# RS323_DB9.net
KiCad netlist of a schematic drawn in EAGLE
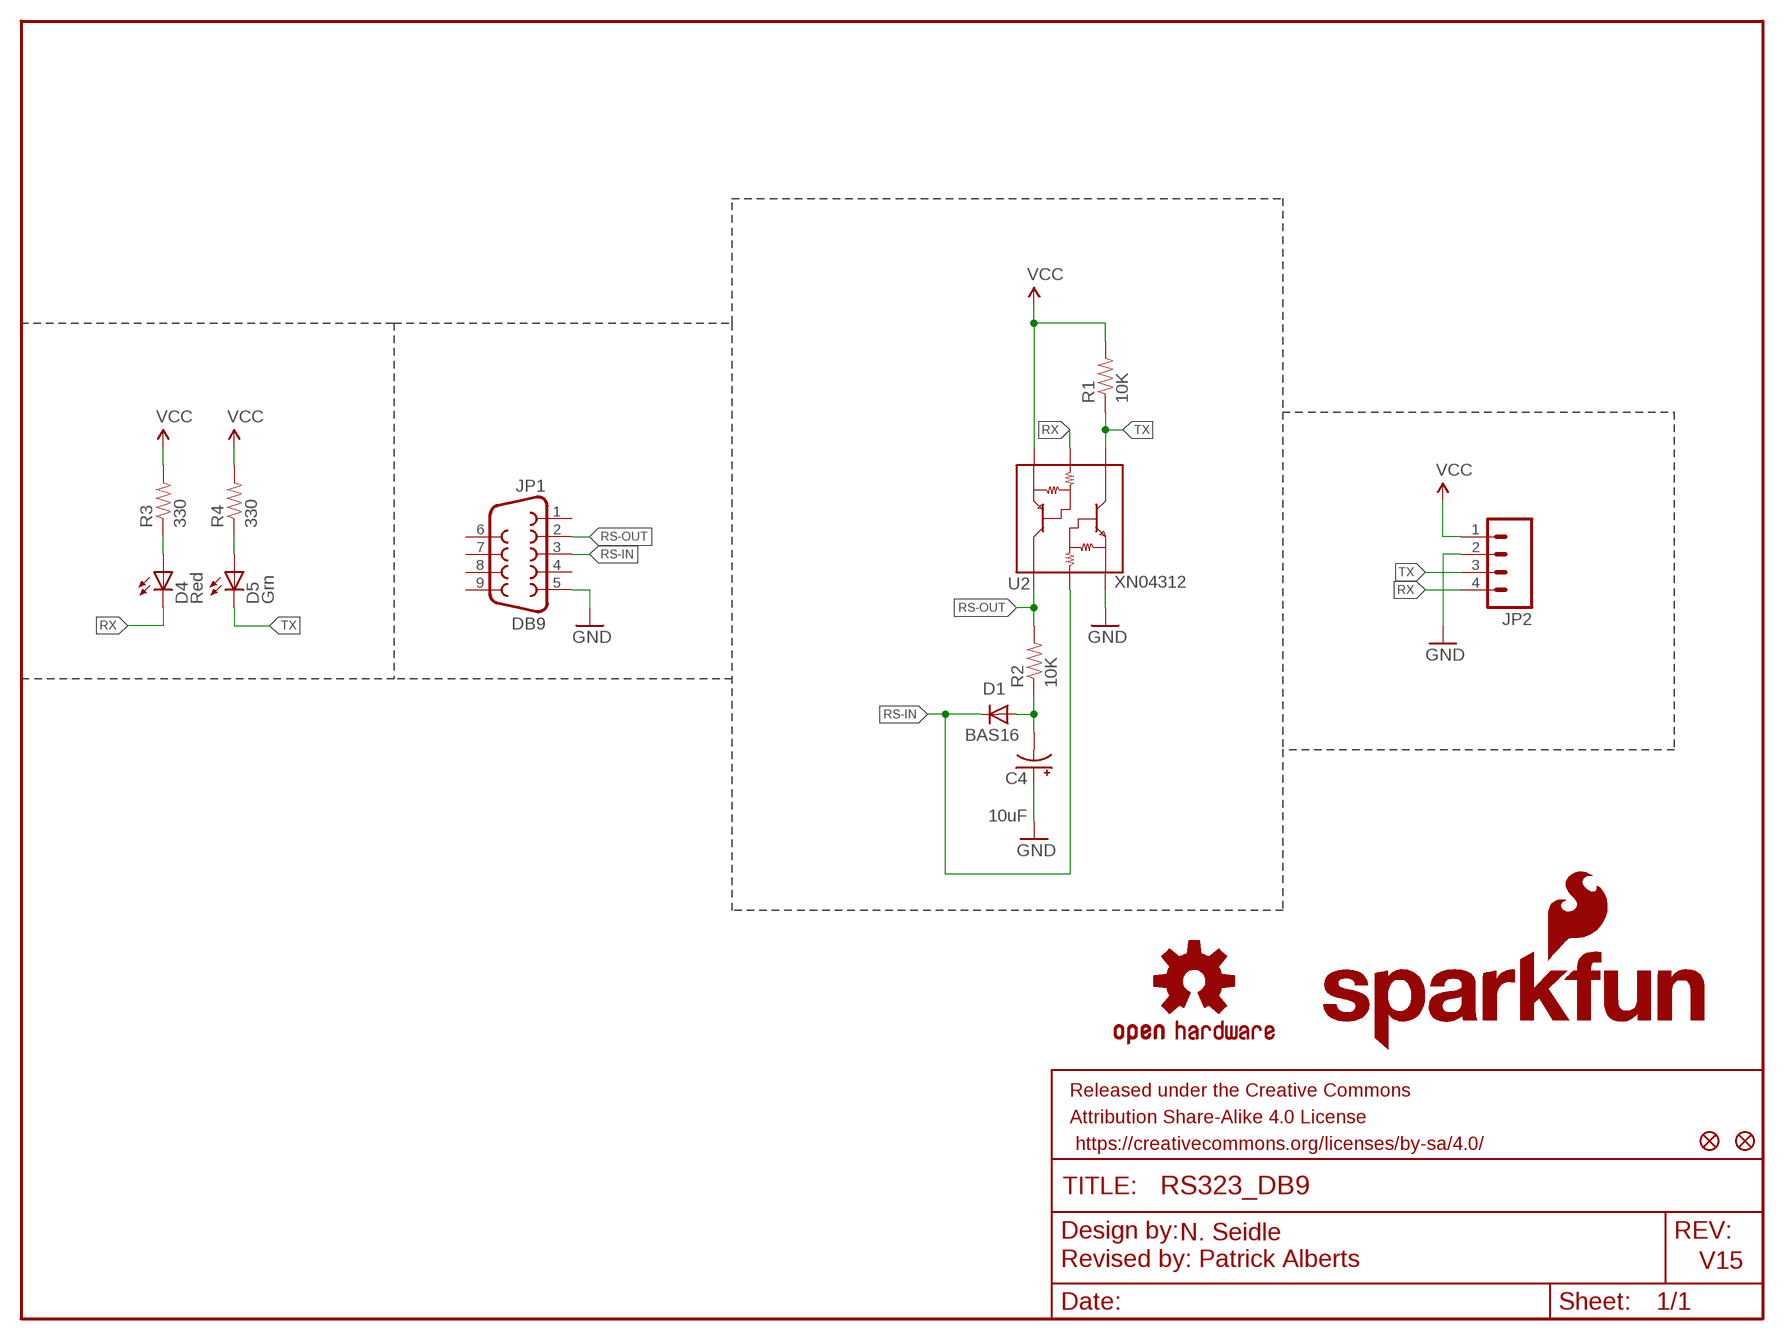
[diagram p0: schematic, sheet 1]

(export (version "E")
  (design (tool "Eeschema 10.0.6"))
  (components
    (comp (ref "C4")
      (value "10uF")
      (footprint "eagle-import:EIA3216")
      (libsource (lib "eagle-import") (part "CAP_POL1206"))
    )
    (comp (ref "D1")
      (value "BAS16")
      (footprint "eagle-import:SOD-323")
      (libsource (lib "eagle-import") (part "DIODESOD"))
    )
    (comp (ref "D4")
      (value "Red")
      (footprint "eagle-import:LED-1206")
      (libsource (lib "eagle-import") (part "LED1206"))
    )
    (comp (ref "D5")
      (value "Grn")
      (footprint "eagle-import:LED-1206")
      (libsource (lib "eagle-import") (part "LED1206"))
    )
    (comp (ref "E$1")
      (value "FIDUCIAL1X2")
      (footprint "eagle-import:FIDUCIAL-1X2")
      (libsource (lib "eagle-import") (part "FIDUCIAL1X2"))
    )
    (comp (ref "E$2")
      (value "FIDUCIAL1X2")
      (footprint "eagle-import:FIDUCIAL-1X2")
      (libsource (lib "eagle-import") (part "FIDUCIAL1X2"))
    )
    (comp (ref "FRAME1")
      (value "FRAME-LETTER")
      (footprint "eagle-import:CREATIVE_COMMONS")
      (fields (field (name "DESIGNER") "NAME"))
      (libsource (lib "eagle-import") (part "FRAME-LETTER"))
    )
    (comp (ref "JP1")
      (value "DB9")
      (footprint "eagle-import:DB9")
      (libsource (lib "eagle-import") (part "DB9FEMALE"))
    )
    (comp (ref "JP2")
      (value "M04PTH")
      (footprint "eagle-import:1X04")
      (libsource (lib "eagle-import") (part "M04PTH"))
    )
    (comp (ref "LOGO1")
      (value "SFE_LOGO_NAME_FLAME.1_INCH")
      (footprint "eagle-import:SFE_LOGO_NAME_FLAME_.1")
      (libsource (lib "eagle-import") (part "SFE_LOGO_NAME_FLAME.1_INCH"))
    )
    (comp (ref "LOGO2")
      (value "OSHW-LOGOM")
      (footprint "eagle-import:OSHW-LOGO-M")
      (libsource (lib "eagle-import") (part "OSHW-LOGOM"))
    )
    (comp (ref "R1")
      (value "10K")
      (footprint "eagle-import:0603-RES")
      (libsource (lib "eagle-import") (part "10KOHM1/10W1%(0603)0603"))
    )
    (comp (ref "R2")
      (value "10K")
      (footprint "eagle-import:0603-RES")
      (libsource (lib "eagle-import") (part "10KOHM1/10W1%(0603)0603"))
    )
    (comp (ref "R3")
      (value "330")
      (footprint "eagle-import:0603-RES")
      (libsource (lib "eagle-import") (part "330OHM1/10W1%(0603)"))
    )
    (comp (ref "R4")
      (value "330")
      (footprint "eagle-import:0603-RES")
      (libsource (lib "eagle-import") (part "330OHM1/10W1%(0603)"))
    )
    (comp (ref "U2")
      (value "XN04312")
      (footprint "eagle-import:SOT23-6")
      (libsource (lib "eagle-import") (part "XN04312SOT"))
    )
  )
  (nets
    (net (code "1") (name "GND") (class "Default")
      (node (ref "C4") (pin "A") (pinfunction "+_A") (pintype "passive"))
      (node (ref "JP1") (pin "5") (pinfunction "5_5") (pintype "passive"))
      (node (ref "JP2") (pin "2") (pinfunction "2_2") (pintype "passive"))
      (node (ref "U2") (pin "6") (pinfunction "E1_6") (pintype "bidirectional"))
    )
    (net (code "2") (name "Net-(C4--)") (class "Default")
      (node (ref "C4") (pin "C") (pinfunction "-_C") (pintype "passive"))
      (node (ref "D1") (pin "2") (pinfunction "A_2") (pintype "passive"))
      (node (ref "R2") (pin "1") (pinfunction "1_1") (pintype "passive"))
    )
    (net (code "3") (name "Net-(D4-PadA)") (class "Default")
      (node (ref "D4") (pin "A") (pinfunction "A_A") (pintype "passive"))
      (node (ref "R3") (pin "1") (pinfunction "1_1") (pintype "passive"))
    )
    (net (code "4") (name "Net-(D5-PadA)") (class "Default")
      (node (ref "D5") (pin "A") (pinfunction "A_A") (pintype "passive"))
      (node (ref "R4") (pin "1") (pinfunction "1_1") (pintype "passive"))
    )
    (net (code "5") (name "RS-IN") (class "Default")
      (node (ref "D1") (pin "1") (pinfunction "C_1") (pintype "passive"))
      (node (ref "JP1") (pin "3") (pinfunction "3_3") (pintype "passive"))
      (node (ref "U2") (pin "5") (pinfunction "B1_5") (pintype "bidirectional"))
    )
    (net (code "6") (name "RS-OUT") (class "Default")
      (node (ref "JP1") (pin "2") (pinfunction "2_2") (pintype "passive"))
      (node (ref "R2") (pin "2") (pinfunction "2_2") (pintype "passive"))
      (node (ref "U2") (pin "4") (pinfunction "C2_4") (pintype "bidirectional"))
    )
    (net (code "7") (name "RX") (class "Default")
      (node (ref "D4") (pin "C") (pinfunction "C_C") (pintype "passive"))
      (node (ref "JP2") (pin "4") (pinfunction "4_4") (pintype "passive"))
      (node (ref "U2") (pin "2") (pinfunction "B2_2") (pintype "bidirectional"))
    )
    (net (code "8") (name "TX") (class "Default")
      (node (ref "D5") (pin "C") (pinfunction "C_C") (pintype "passive"))
      (node (ref "JP2") (pin "3") (pinfunction "3_3") (pintype "passive"))
      (node (ref "R1") (pin "1") (pinfunction "1_1") (pintype "passive"))
      (node (ref "U2") (pin "1") (pinfunction "C1_1") (pintype "bidirectional"))
    )
    (net (code "9") (name "VCC") (class "Default")
      (node (ref "JP2") (pin "1") (pinfunction "1_1") (pintype "passive"))
      (node (ref "R1") (pin "2") (pinfunction "2_2") (pintype "passive"))
      (node (ref "R3") (pin "2") (pinfunction "2_2") (pintype "passive"))
      (node (ref "R4") (pin "2") (pinfunction "2_2") (pintype "passive"))
      (node (ref "U2") (pin "3") (pinfunction "E2_3") (pintype "bidirectional"))
    )
    (net (code "10") (name "unconnected-(JP1-Pad1)") (class "Default")
      (node (ref "JP1") (pin "1") (pinfunction "1_1") (pintype "passive"))
    )
    (net (code "11") (name "unconnected-(JP1-Pad4)") (class "Default")
      (node (ref "JP1") (pin "4") (pinfunction "4_4") (pintype "passive"))
    )
    (net (code "12") (name "unconnected-(JP1-Pad6)") (class "Default")
      (node (ref "JP1") (pin "6") (pinfunction "6_6") (pintype "passive"))
    )
    (net (code "13") (name "unconnected-(JP1-Pad7)") (class "Default")
      (node (ref "JP1") (pin "7") (pinfunction "7_7") (pintype "passive"))
    )
    (net (code "14") (name "unconnected-(JP1-Pad8)") (class "Default")
      (node (ref "JP1") (pin "8") (pinfunction "8_8") (pintype "passive"))
    )
    (net (code "15") (name "unconnected-(JP1-Pad9)") (class "Default")
      (node (ref "JP1") (pin "9") (pinfunction "9_9") (pintype "passive"))
    )
  )
)
